# ProPrj_PMS5003-feathwerwing-v1_2025-06-3.net
KiCad netlist of a schematic drawn in EasyEDA Pro
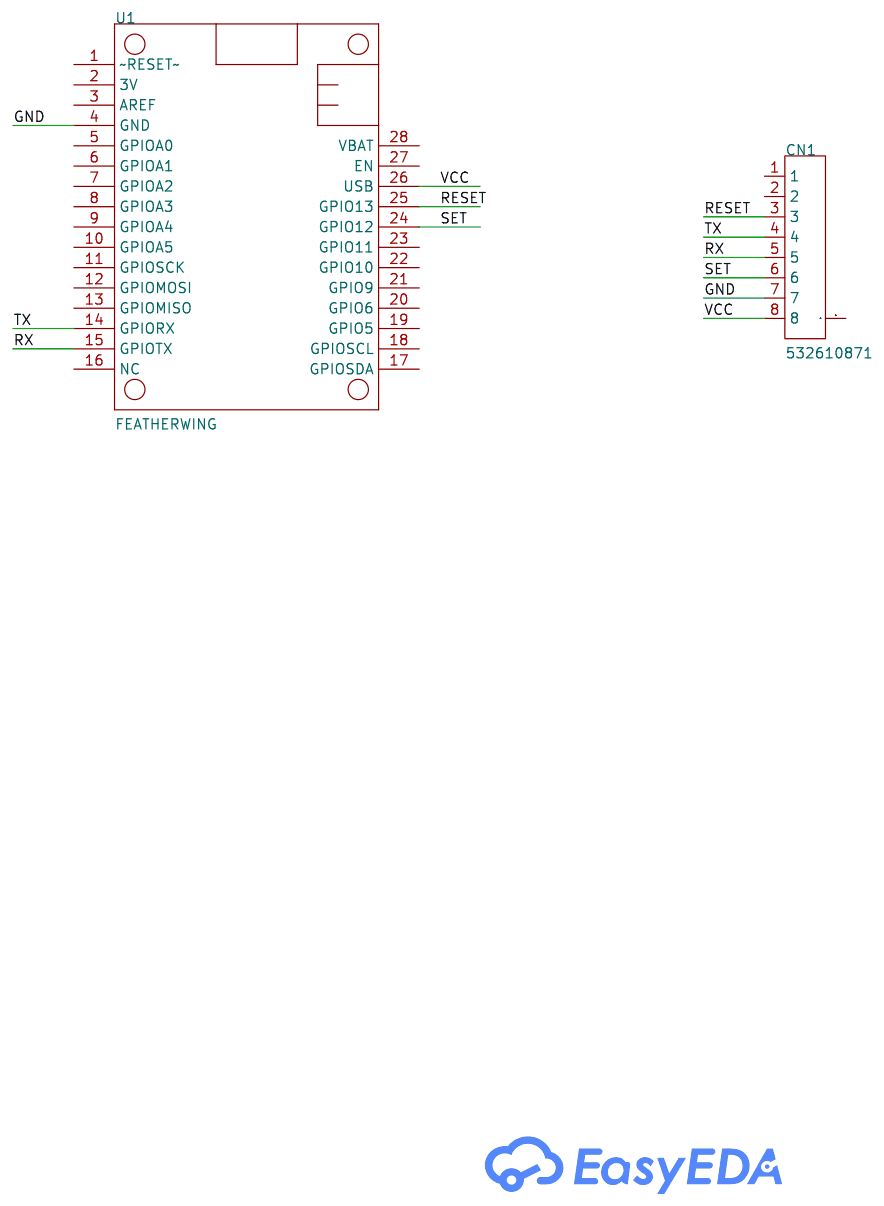
[diagram p0: schematic sheet]

(export (version "E")
  (design (tool "Eeschema 10.0.6"))
  (components
    (comp (ref "CN1")
      (value "532610871")
      (footprint "easyedapro:CONN-SMD_532610871")
      (fields (field (name "Manufacturer") "MOLEX"))
      (libsource (lib "easyedapro") (part "532610871"))
    )
    (comp (ref "U1")
      (value "FEATHERWING")
      (footprint "easyedapro:FEATHERWING")
      (libsource (lib "easyedapro") (part "FEATHERWING"))
    )
  )
  (nets
    (net (code "1") (name "/GND") (class "Default")
      (node (ref "CN1") (pin "7") (pinfunction "7_7") (pintype "unspecified"))
      (node (ref "U1") (pin "4") (pinfunction "GND_4") (pintype "unspecified"))
    )
    (net (code "2") (name "/RESET") (class "Default")
      (node (ref "CN1") (pin "3") (pinfunction "3_3") (pintype "unspecified"))
      (node (ref "U1") (pin "25") (pinfunction "GPIO13_25") (pintype "bidirectional"))
    )
    (net (code "3") (name "/RX") (class "Default")
      (node (ref "CN1") (pin "5") (pinfunction "5_5") (pintype "unspecified"))
      (node (ref "U1") (pin "15") (pinfunction "GPIOTX_15") (pintype "bidirectional"))
    )
    (net (code "4") (name "/SET") (class "Default")
      (node (ref "CN1") (pin "6") (pinfunction "6_6") (pintype "unspecified"))
      (node (ref "U1") (pin "24") (pinfunction "GPIO12_24") (pintype "bidirectional"))
    )
    (net (code "5") (name "/TX") (class "Default")
      (node (ref "CN1") (pin "4") (pinfunction "4_4") (pintype "unspecified"))
      (node (ref "U1") (pin "14") (pinfunction "GPIORX_14") (pintype "bidirectional"))
    )
    (net (code "6") (name "/VCC") (class "Default")
      (node (ref "CN1") (pin "8") (pinfunction "8_8") (pintype "unspecified"))
      (node (ref "U1") (pin "26") (pinfunction "USB_26") (pintype "unspecified"))
    )
    (net (code "7") (name "unconnected-(CN1-Pad0)") (class "Default")
      (node (ref "CN1") (pin "0") (pinfunction "0_0") (pintype "unspecified"))
    )
    (net (code "8") (name "unconnected-(CN1-Pad1)") (class "Default")
      (node (ref "CN1") (pin "1") (pinfunction "1_1") (pintype "unspecified"))
    )
    (net (code "9") (name "unconnected-(CN1-Pad2)") (class "Default")
      (node (ref "CN1") (pin "2") (pinfunction "2_2") (pintype "unspecified"))
    )
    (net (code "10") (name "unconnected-(U1-3V-Pad2)") (class "Default")
      (node (ref "U1") (pin "2") (pinfunction "3V_2") (pintype "unspecified"))
    )
    (net (code "11") (name "unconnected-(U1-AREF-Pad3)") (class "Default")
      (node (ref "U1") (pin "3") (pinfunction "AREF_3") (pintype "unspecified"))
    )
    (net (code "12") (name "unconnected-(U1-EN-Pad27)") (class "Default")
      (node (ref "U1") (pin "27") (pinfunction "EN_27") (pintype "unspecified"))
    )
    (net (code "13") (name "unconnected-(U1-GPIO5-Pad19)") (class "Default")
      (node (ref "U1") (pin "19") (pinfunction "GPIO5_19") (pintype "bidirectional"))
    )
    (net (code "14") (name "unconnected-(U1-GPIO6-Pad20)") (class "Default")
      (node (ref "U1") (pin "20") (pinfunction "GPIO6_20") (pintype "bidirectional"))
    )
    (net (code "15") (name "unconnected-(U1-GPIO9-Pad21)") (class "Default")
      (node (ref "U1") (pin "21") (pinfunction "GPIO9_21") (pintype "bidirectional"))
    )
    (net (code "16") (name "unconnected-(U1-GPIO10-Pad22)") (class "Default")
      (node (ref "U1") (pin "22") (pinfunction "GPIO10_22") (pintype "bidirectional"))
    )
    (net (code "17") (name "unconnected-(U1-GPIO11-Pad23)") (class "Default")
      (node (ref "U1") (pin "23") (pinfunction "GPIO11_23") (pintype "bidirectional"))
    )
    (net (code "18") (name "unconnected-(U1-GPIOA0-Pad5)") (class "Default")
      (node (ref "U1") (pin "5") (pinfunction "GPIOA0_5") (pintype "bidirectional"))
    )
    (net (code "19") (name "unconnected-(U1-GPIOA1-Pad6)") (class "Default")
      (node (ref "U1") (pin "6") (pinfunction "GPIOA1_6") (pintype "bidirectional"))
    )
    (net (code "20") (name "unconnected-(U1-GPIOA2-Pad7)") (class "Default")
      (node (ref "U1") (pin "7") (pinfunction "GPIOA2_7") (pintype "bidirectional"))
    )
    (net (code "21") (name "unconnected-(U1-GPIOA3-Pad8)") (class "Default")
      (node (ref "U1") (pin "8") (pinfunction "GPIOA3_8") (pintype "bidirectional"))
    )
    (net (code "22") (name "unconnected-(U1-GPIOA4-Pad9)") (class "Default")
      (node (ref "U1") (pin "9") (pinfunction "GPIOA4_9") (pintype "bidirectional"))
    )
    (net (code "23") (name "unconnected-(U1-GPIOA5-Pad10)") (class "Default")
      (node (ref "U1") (pin "10") (pinfunction "GPIOA5_10") (pintype "bidirectional"))
    )
    (net (code "24") (name "unconnected-(U1-GPIOMISO-Pad13)") (class "Default")
      (node (ref "U1") (pin "13") (pinfunction "GPIOMISO_13") (pintype "bidirectional"))
    )
    (net (code "25") (name "unconnected-(U1-GPIOMOSI-Pad12)") (class "Default")
      (node (ref "U1") (pin "12") (pinfunction "GPIOMOSI_12") (pintype "bidirectional"))
    )
    (net (code "26") (name "unconnected-(U1-GPIOSCK-Pad11)") (class "Default")
      (node (ref "U1") (pin "11") (pinfunction "GPIOSCK_11") (pintype "bidirectional"))
    )
    (net (code "27") (name "unconnected-(U1-GPIOSCL-Pad18)") (class "Default")
      (node (ref "U1") (pin "18") (pinfunction "GPIOSCL_18") (pintype "bidirectional"))
    )
    (net (code "28") (name "unconnected-(U1-GPIOSDA-Pad17)") (class "Default")
      (node (ref "U1") (pin "17") (pinfunction "GPIOSDA_17") (pintype "bidirectional"))
    )
    (net (code "29") (name "unconnected-(U1-NC-Pad16)") (class "Default")
      (node (ref "U1") (pin "16") (pinfunction "NC_16") (pintype "unspecified"))
    )
    (net (code "30") (name "unconnected-(U1-VBAT-Pad28)") (class "Default")
      (node (ref "U1") (pin "28") (pinfunction "VBAT_28") (pintype "unspecified"))
    )
    (net (code "31") (name "unconnected-(U1-~RESET~-Pad1)") (class "Default")
      (node (ref "U1") (pin "1") (pinfunction "~RESET~_1") (pintype "input"))
    )
  )
)
